# crystal-test.net
KiCad netlist of a schematic drawn in EAGLE
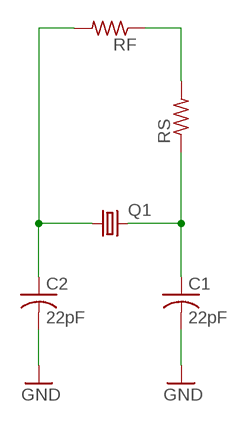
[diagram p0: schematic, sheet 1]

(export (version "E")
  (design (tool "Eeschema 10.0.6"))
  (components
    (comp (ref "C1")
      (value "22pF")
      (footprint "eagle-import:C1206K")
      (libsource (lib "eagle-import") (part "CAPACITORC1206K"))
    )
    (comp (ref "C2")
      (value "22pF")
      (footprint "eagle-import:C1206K")
      (libsource (lib "eagle-import") (part "CAPACITORC1206K"))
    )
    (comp (ref "Q1")
      (value "CRYSTALTC26V")
      (footprint "eagle-import:TC26V")
      (libsource (lib "eagle-import") (part "CRYSTALTC26V"))
    )
    (comp (ref "RF")
      (value "RESISTORR1206")
      (footprint "eagle-import:R1206")
      (libsource (lib "eagle-import") (part "RESISTORR1206"))
    )
    (comp (ref "RS")
      (value "RESISTORR1206")
      (footprint "eagle-import:R1206")
      (libsource (lib "eagle-import") (part "RESISTORR1206"))
    )
  )
  (nets
    (net (code "1") (name "GND") (class "Default")
      (node (ref "C1") (pin "2") (pinfunction "2_2") (pintype "passive"))
      (node (ref "C2") (pin "2") (pinfunction "2_2") (pintype "passive"))
    )
    (net (code "2") (name "Net-(C1-Pad1)") (class "Default")
      (node (ref "C1") (pin "1") (pinfunction "1_1") (pintype "passive"))
      (node (ref "Q1") (pin "2") (pinfunction "2_2") (pintype "passive"))
      (node (ref "RS") (pin "1") (pinfunction "1_1") (pintype "passive"))
    )
    (net (code "3") (name "Net-(C2-Pad1)") (class "Default")
      (node (ref "C2") (pin "1") (pinfunction "1_1") (pintype "passive"))
      (node (ref "Q1") (pin "1") (pinfunction "1_1") (pintype "passive"))
      (node (ref "RF") (pin "2") (pinfunction "2_2") (pintype "passive"))
    )
    (net (code "4") (name "Net-(RF-Pad1)") (class "Default")
      (node (ref "RF") (pin "1") (pinfunction "1_1") (pintype "passive"))
      (node (ref "RS") (pin "2") (pinfunction "2_2") (pintype "passive"))
    )
  )
)
